# Sheet2.net
KiCad netlist of a schematic drawn in Altium Designer
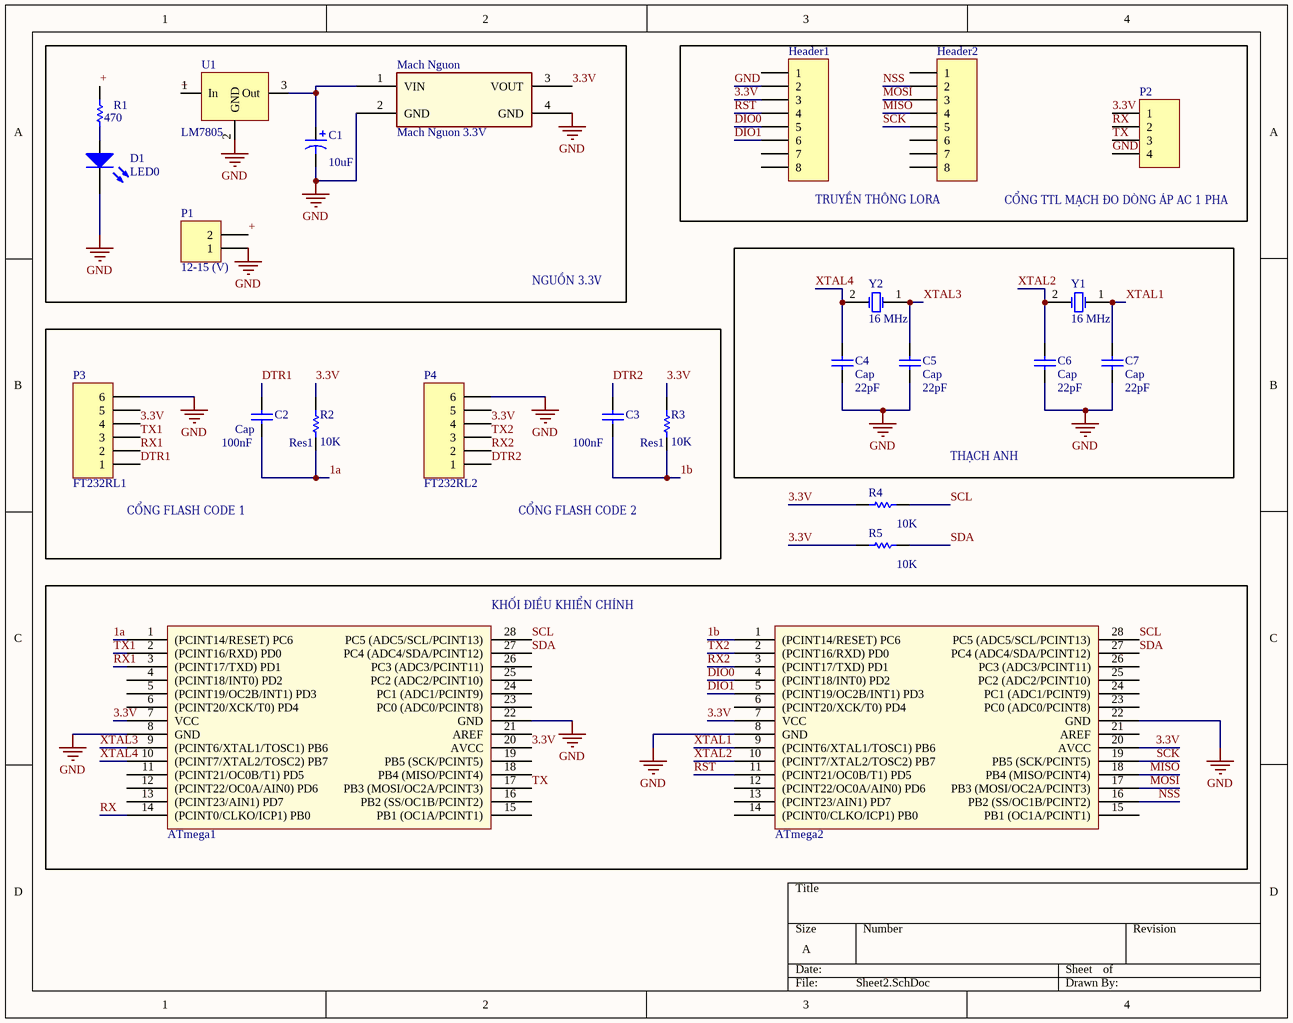
[diagram p0: Sheet2.SchDoc]

(export (version "E")
  (design (tool "Eeschema 10.0.6"))
  (components
    (comp (ref "ATmega1")
      (value "ATmega328P")
      (footprint "DIP794W46P254L2967H457Q28B")
      (libsource (lib "ATMEGA328") (part "ATmega328P"))
    )
    (comp (ref "ATmega2")
      (value "ATmega328P")
      (footprint "DIP794W46P254L2967H457Q28B")
      (libsource (lib "ATMEGA328") (part "ATmega328P"))
    )
    (comp (ref "C1")
      (value "10uF")
      (footprint "RB7.6-15")
      (description "Polarized Capacitor (Radial)")
      (fields (field (name "Comment") "Cap Pol1") (field (name "PUBLISHER") "Altium Limited"))
      (libsource (lib "Miscellaneous Devices") (part "Cap Pol1"))
    )
    (comp (ref "C2")
      (value "Cap")
      (footprint "RAD-0.3")
      (description "Capacitor")
      (fields (field (name "ALTIUM_VALUE") "100nF") (field (name "PUBLISHER") "Altium Limited"))
      (libsource (lib "Miscellaneous Devices") (part "Cap"))
    )
    (comp (ref "C3")
      (value "100nF")
      (footprint "RAD-0.3")
      (description "Capacitor")
      (fields (field (name "Comment") "Cap3") (field (name "PUBLISHER") "Altium Limited"))
      (libsource (lib "Miscellaneous Devices") (part "Cap"))
    )
    (comp (ref "C4")
      (value "Cap")
      (footprint "RAD-0.3")
      (description "Capacitor")
      (fields (field (name "ALTIUM_VALUE") "22pF") (field (name "PUBLISHER") "Altium Limited"))
      (libsource (lib "Miscellaneous Devices") (part "Cap"))
    )
    (comp (ref "C5")
      (value "Cap")
      (footprint "RAD-0.3")
      (description "Capacitor")
      (fields (field (name "ALTIUM_VALUE") "22pF") (field (name "PUBLISHER") "Altium Limited"))
      (libsource (lib "Miscellaneous Devices") (part "Cap"))
    )
    (comp (ref "C6")
      (value "Cap")
      (footprint "RAD-0.3")
      (description "Capacitor")
      (fields (field (name "ALTIUM_VALUE") "22pF") (field (name "PUBLISHER") "Altium Limited"))
      (libsource (lib "Miscellaneous Devices") (part "Cap"))
    )
    (comp (ref "C7")
      (value "Cap")
      (footprint "RAD-0.3")
      (description "Capacitor")
      (fields (field (name "ALTIUM_VALUE") "22pF") (field (name "PUBLISHER") "Altium Limited"))
      (libsource (lib "Miscellaneous Devices") (part "Cap"))
    )
    (comp (ref "D1")
      (value "LED0")
      (footprint "LED-0")
      (description "Typical INFRARED GaAs LED")
      (fields (field (name "PUBLISHER") "Altium Limited"))
      (libsource (lib "Miscellaneous Devices") (part "LED0"))
    )
    (comp (ref "Header1")
      (value "~")
      (footprint "HDR1X8")
      (description "Header, 8-Pin")
      (fields (field (name "PUBLISHER") "Altium Limited"))
      (libsource (lib "Miscellaneous Connectors") (part "Header 8"))
    )
    (comp (ref "Header2")
      (value "~")
      (footprint "HDR1X8")
      (description "Header, 8-Pin")
      (fields (field (name "PUBLISHER") "Altium Limited"))
      (libsource (lib "Miscellaneous Connectors") (part "Header 8"))
    )
    (comp (ref "Mach Nguon")
      (value "Mach Nguon 3.3V")
      (footprint "PCBComponent_1")
      (libsource (lib "MachNguon3.3V") (part "Component_1"))
    )
    (comp (ref "P1")
      (value "12-15 (V)")
      (footprint "HDR1X2")
      (description "Header, 2-Pin")
      (fields (field (name "PUBLISHER") "Altium Limited"))
      (libsource (lib "Miscellaneous Connectors") (part "Header 2"))
    )
    (comp (ref "P2")
      (value "Header 4")
      (footprint "HDR1X4")
      (description "Header, 4-Pin")
      (fields (field (name "PUBLISHER") "Altium Limited"))
      (libsource (lib "Miscellaneous Connectors") (part "Header 4"))
    )
    (comp (ref "P3")
      (value "FT232RL1")
      (footprint "HDR1X6")
      (description "Header, 6-Pin")
      (fields (field (name "PUBLISHER") "Altium Limited"))
      (libsource (lib "Miscellaneous Connectors") (part "Header 6"))
    )
    (comp (ref "P4")
      (value "FT232RL2")
      (footprint "HDR1X6")
      (description "Header, 6-Pin")
      (fields (field (name "PUBLISHER") "Altium Limited"))
      (libsource (lib "Miscellaneous Connectors") (part "Header 6"))
    )
    (comp (ref "R1")
      (value "470")
      (footprint "AXIAL-0.3")
      (description "Resistor")
      (fields (field (name "Comment") "Res1") (field (name "PUBLISHER") "Altium Limited"))
      (libsource (lib "Miscellaneous Devices") (part "Res1"))
    )
    (comp (ref "R2")
      (value "Res1")
      (footprint "AXIAL-0.3")
      (description "Resistor")
      (fields (field (name "ALTIUM_VALUE") "10K") (field (name "PUBLISHER") "Altium Limited"))
      (libsource (lib "Miscellaneous Devices") (part "Res1"))
    )
    (comp (ref "R3")
      (value "Res1")
      (footprint "AXIAL-0.3")
      (description "Resistor")
      (fields (field (name "ALTIUM_VALUE") "10K") (field (name "PUBLISHER") "Altium Limited"))
      (libsource (lib "Miscellaneous Devices") (part "Res1"))
    )
    (comp (ref "R4")
      (value "10K")
      (footprint "AXIAL-0.3")
      (description "Resistor")
      (fields (field (name "Comment") "Res1") (field (name "PUBLISHER") "Altium Limited"))
      (libsource (lib "Miscellaneous Devices") (part "Res1"))
    )
    (comp (ref "R5")
      (value "10K")
      (footprint "AXIAL-0.3")
      (description "Resistor")
      (fields (field (name "Comment") "Res1") (field (name "PUBLISHER") "Altium Limited"))
      (libsource (lib "Miscellaneous Devices") (part "Res1"))
    )
    (comp (ref "U1")
      (value "LM7805")
      (footprint "TO92-")
      (description "IC REG LIN 5V 1A")
      (libsource (lib "LM7805") (part "LM7805"))
    )
    (comp (ref "Y1")
      (value "16 MHz")
      (footprint "R38")
      (description "Crystal Oscillator")
      (fields (field (name "PUBLISHER") "Altium Limited"))
      (libsource (lib "Miscellaneous Devices") (part "XTAL"))
    )
    (comp (ref "Y2")
      (value "16 MHz")
      (footprint "R38")
      (description "Crystal Oscillator")
      (fields (field (name "PUBLISHER") "Altium Limited"))
      (libsource (lib "Miscellaneous Devices") (part "XTAL"))
    )
  )
  (nets
    (net (code "1") (name "/+") (class "Default")
      (node (ref "P1") (pin "2") (pinfunction "2_2") (pintype "passive"))
      (node (ref "R1") (pin "2") (pinfunction "2_2") (pintype "passive"))
      (node (ref "U1") (pin "1") (pinfunction "In_1") (pintype "passive"))
    )
    (net (code "2") (name "/1a") (class "Default")
      (node (ref "ATmega1") (pin "1") (pinfunction "(PCINT14/RESET)_PC6_1") (pintype "passive"))
      (node (ref "C2") (pin "1") (pinfunction "1_1") (pintype "passive"))
      (node (ref "R2") (pin "1") (pinfunction "1_1") (pintype "passive"))
    )
    (net (code "3") (name "/1b") (class "Default")
      (node (ref "ATmega2") (pin "1") (pinfunction "(PCINT14/RESET)_PC6_1") (pintype "passive"))
      (node (ref "C3") (pin "1") (pinfunction "1_1") (pintype "passive"))
      (node (ref "R3") (pin "1") (pinfunction "1_1") (pintype "passive"))
    )
    (net (code "4") (name "/3.3V") (class "Default")
      (node (ref "ATmega1") (pin "20") (pinfunction "AVCC_20") (pintype "passive"))
      (node (ref "ATmega1") (pin "7") (pinfunction "VCC_7") (pintype "passive"))
      (node (ref "ATmega2") (pin "20") (pinfunction "AVCC_20") (pintype "passive"))
      (node (ref "ATmega2") (pin "7") (pinfunction "VCC_7") (pintype "passive"))
      (node (ref "Header1") (pin "3") (pinfunction "3_3") (pintype "passive"))
      (node (ref "Mach Nguon") (pin "3") (pinfunction "VOUT_3") (pintype "passive"))
      (node (ref "P2") (pin "1") (pinfunction "1_1") (pintype "passive"))
      (node (ref "P3") (pin "4") (pinfunction "4_4") (pintype "passive"))
      (node (ref "P4") (pin "4") (pinfunction "4_4") (pintype "passive"))
      (node (ref "R2") (pin "2") (pinfunction "2_2") (pintype "passive"))
      (node (ref "R3") (pin "2") (pinfunction "2_2") (pintype "passive"))
      (node (ref "R4") (pin "1") (pinfunction "1_1") (pintype "passive"))
      (node (ref "R5") (pin "1") (pinfunction "1_1") (pintype "passive"))
    )
    (net (code "5") (name "/DIO0") (class "Default")
      (node (ref "ATmega2") (pin "4") (pinfunction "(PCINT18/INT0)_PD2_4") (pintype "passive"))
      (node (ref "Header1") (pin "5") (pinfunction "5_5") (pintype "passive"))
    )
    (net (code "6") (name "/DIO1") (class "Default")
      (node (ref "ATmega2") (pin "5") (pinfunction "(PCINT19/OC2B/INT1)_PD3_5") (pintype "passive"))
      (node (ref "Header1") (pin "6") (pinfunction "6_6") (pintype "passive"))
    )
    (net (code "7") (name "/DTR1") (class "Default")
      (node (ref "C2") (pin "2") (pinfunction "2_2") (pintype "passive"))
      (node (ref "P3") (pin "1") (pinfunction "1_1") (pintype "passive"))
    )
    (net (code "8") (name "/DTR2") (class "Default")
      (node (ref "C3") (pin "2") (pinfunction "2_2") (pintype "passive"))
      (node (ref "P4") (pin "1") (pinfunction "1_1") (pintype "passive"))
    )
    (net (code "9") (name "/MISO") (class "Default")
      (node (ref "ATmega2") (pin "18") (pinfunction "PB4_(MISO/PCINT4)_18") (pintype "passive"))
      (node (ref "Header2") (pin "4") (pinfunction "4_4") (pintype "passive"))
    )
    (net (code "10") (name "/MOSI") (class "Default")
      (node (ref "ATmega2") (pin "17") (pinfunction "PB3_(MOSI/OC2A/PCINT3)_17") (pintype "passive"))
      (node (ref "Header2") (pin "3") (pinfunction "3_3") (pintype "passive"))
    )
    (net (code "11") (name "/NSS") (class "Default")
      (node (ref "ATmega2") (pin "16") (pinfunction "PB2_(SS/OC1B/PCINT2)_16") (pintype "passive"))
      (node (ref "Header2") (pin "2") (pinfunction "2_2") (pintype "passive"))
    )
    (net (code "12") (name "/RST") (class "Default")
      (node (ref "ATmega2") (pin "11") (pinfunction "(PCINT21/OC0B/T1)_PD5_11") (pintype "passive"))
      (node (ref "Header1") (pin "4") (pinfunction "4_4") (pintype "passive"))
    )
    (net (code "13") (name "/RX") (class "Default")
      (node (ref "ATmega1") (pin "14") (pinfunction "(PCINT0/CLKO/ICP1)_PB0_14") (pintype "passive"))
      (node (ref "P2") (pin "2") (pinfunction "2_2") (pintype "passive"))
    )
    (net (code "14") (name "/RX1") (class "Default")
      (node (ref "ATmega1") (pin "3") (pinfunction "(PCINT17/TXD)_PD1_3") (pintype "passive"))
      (node (ref "P3") (pin "2") (pinfunction "2_2") (pintype "passive"))
    )
    (net (code "15") (name "/RX2") (class "Default")
      (node (ref "ATmega2") (pin "3") (pinfunction "(PCINT17/TXD)_PD1_3") (pintype "passive"))
      (node (ref "P4") (pin "2") (pinfunction "2_2") (pintype "passive"))
    )
    (net (code "16") (name "/SCK") (class "Default")
      (node (ref "ATmega2") (pin "19") (pinfunction "PB5_(SCK/PCINT5)_19") (pintype "passive"))
      (node (ref "Header2") (pin "5") (pinfunction "5_5") (pintype "passive"))
    )
    (net (code "17") (name "/SCL") (class "Default")
      (node (ref "ATmega1") (pin "28") (pinfunction "PC5_(ADC5/SCL/PCINT13)_28") (pintype "passive"))
      (node (ref "ATmega2") (pin "28") (pinfunction "PC5_(ADC5/SCL/PCINT13)_28") (pintype "passive"))
      (node (ref "R4") (pin "2") (pinfunction "2_2") (pintype "passive"))
    )
    (net (code "18") (name "/SDA") (class "Default")
      (node (ref "ATmega1") (pin "27") (pinfunction "PC4_(ADC4/SDA/PCINT12)_27") (pintype "passive"))
      (node (ref "ATmega2") (pin "27") (pinfunction "PC4_(ADC4/SDA/PCINT12)_27") (pintype "passive"))
      (node (ref "R5") (pin "2") (pinfunction "2_2") (pintype "passive"))
    )
    (net (code "19") (name "/TX") (class "Default")
      (node (ref "ATmega1") (pin "17") (pinfunction "PB3_(MOSI/OC2A/PCINT3)_17") (pintype "passive"))
      (node (ref "P2") (pin "3") (pinfunction "3_3") (pintype "passive"))
    )
    (net (code "20") (name "/TX1") (class "Default")
      (node (ref "ATmega1") (pin "2") (pinfunction "(PCINT16/RXD)_PD0_2") (pintype "passive"))
      (node (ref "P3") (pin "3") (pinfunction "3_3") (pintype "passive"))
    )
    (net (code "21") (name "/TX2") (class "Default")
      (node (ref "ATmega2") (pin "2") (pinfunction "(PCINT16/RXD)_PD0_2") (pintype "passive"))
      (node (ref "P4") (pin "3") (pinfunction "3_3") (pintype "passive"))
    )
    (net (code "22") (name "/XTAL1") (class "Default")
      (node (ref "ATmega2") (pin "9") (pinfunction "(PCINT6/XTAL1/TOSC1)_PB6_9") (pintype "passive"))
      (node (ref "C7") (pin "2") (pinfunction "2_2") (pintype "passive"))
      (node (ref "Y1") (pin "1") (pinfunction "OSC1_1") (pintype "passive"))
    )
    (net (code "23") (name "/XTAL2") (class "Default")
      (node (ref "ATmega2") (pin "10") (pinfunction "(PCINT7/XTAL2/TOSC2)_PB7_10") (pintype "passive"))
      (node (ref "C6") (pin "2") (pinfunction "2_2") (pintype "passive"))
      (node (ref "Y1") (pin "2") (pinfunction "OSC2_2") (pintype "passive"))
    )
    (net (code "24") (name "/XTAL3") (class "Default")
      (node (ref "ATmega1") (pin "9") (pinfunction "(PCINT6/XTAL1/TOSC1)_PB6_9") (pintype "passive"))
      (node (ref "C5") (pin "2") (pinfunction "2_2") (pintype "passive"))
      (node (ref "Y2") (pin "1") (pinfunction "OSC1_1") (pintype "passive"))
    )
    (net (code "25") (name "/XTAL4") (class "Default")
      (node (ref "ATmega1") (pin "10") (pinfunction "(PCINT7/XTAL2/TOSC2)_PB7_10") (pintype "passive"))
      (node (ref "C4") (pin "2") (pinfunction "2_2") (pintype "passive"))
      (node (ref "Y2") (pin "2") (pinfunction "OSC2_2") (pintype "passive"))
    )
    (net (code "26") (name "GND") (class "Default")
      (node (ref "ATmega1") (pin "22") (pinfunction "GND_22") (pintype "passive"))
      (node (ref "ATmega1") (pin "8") (pinfunction "GND_8") (pintype "passive"))
      (node (ref "ATmega2") (pin "22") (pinfunction "GND_22") (pintype "passive"))
      (node (ref "ATmega2") (pin "8") (pinfunction "GND_8") (pintype "passive"))
      (node (ref "C1") (pin "2") (pinfunction "2_2") (pintype "passive"))
      (node (ref "C4") (pin "1") (pinfunction "1_1") (pintype "passive"))
      (node (ref "C5") (pin "1") (pinfunction "1_1") (pintype "passive"))
      (node (ref "C6") (pin "1") (pinfunction "1_1") (pintype "passive"))
      (node (ref "C7") (pin "1") (pinfunction "1_1") (pintype "passive"))
      (node (ref "D1") (pin "2") (pinfunction "K_2") (pintype "passive"))
      (node (ref "Header1") (pin "2") (pinfunction "2_2") (pintype "passive"))
      (node (ref "Mach Nguon") (pin "2") (pinfunction "GND_2") (pintype "passive"))
      (node (ref "Mach Nguon") (pin "4") (pinfunction "GND_4") (pintype "passive"))
      (node (ref "P1") (pin "1") (pinfunction "1_1") (pintype "passive"))
      (node (ref "P2") (pin "4") (pinfunction "4_4") (pintype "passive"))
      (node (ref "P3") (pin "6") (pinfunction "6_6") (pintype "passive"))
      (node (ref "P4") (pin "6") (pinfunction "6_6") (pintype "passive"))
      (node (ref "U1") (pin "2") (pinfunction "GND_2") (pintype "passive"))
    )
    (net (code "27") (name "Net-(D1-A)") (class "Default")
      (node (ref "D1") (pin "1") (pinfunction "A_1") (pintype "passive"))
      (node (ref "R1") (pin "1") (pinfunction "1_1") (pintype "passive"))
    )
    (net (code "28") (name "Net-(Mach Nguon-VIN)") (class "Default")
      (node (ref "C1") (pin "1") (pinfunction "1_1") (pintype "passive"))
      (node (ref "Mach Nguon") (pin "1") (pinfunction "VIN_1") (pintype "passive"))
      (node (ref "U1") (pin "3") (pinfunction "Out_3") (pintype "passive"))
    )
    (net (code "29") (name "unconnected-(ATmega1-(PCINT18{slash}INT0)_PD2-Pad4)") (class "Default")
      (node (ref "ATmega1") (pin "4") (pinfunction "(PCINT18/INT0)_PD2_4") (pintype "passive"))
    )
    (net (code "30") (name "unconnected-(ATmega1-(PCINT19{slash}OC2B{slash}INT1)_PD3-Pad5)") (class "Default")
      (node (ref "ATmega1") (pin "5") (pinfunction "(PCINT19/OC2B/INT1)_PD3_5") (pintype "passive"))
    )
    (net (code "31") (name "unconnected-(ATmega1-(PCINT20{slash}XCK{slash}T0)_PD4-Pad6)") (class "Default")
      (node (ref "ATmega1") (pin "6") (pinfunction "(PCINT20/XCK/T0)_PD4_6") (pintype "passive"))
    )
    (net (code "32") (name "unconnected-(ATmega1-(PCINT21{slash}OC0B{slash}T1)_PD5-Pad11)") (class "Default")
      (node (ref "ATmega1") (pin "11") (pinfunction "(PCINT21/OC0B/T1)_PD5_11") (pintype "passive"))
    )
    (net (code "33") (name "unconnected-(ATmega1-(PCINT22{slash}OC0A{slash}AIN0)_PD6-Pad12)") (class "Default")
      (node (ref "ATmega1") (pin "12") (pinfunction "(PCINT22/OC0A/AIN0)_PD6_12") (pintype "passive"))
    )
    (net (code "34") (name "unconnected-(ATmega1-(PCINT23{slash}AIN1)_PD7-Pad13)") (class "Default")
      (node (ref "ATmega1") (pin "13") (pinfunction "(PCINT23/AIN1)_PD7_13") (pintype "passive"))
    )
    (net (code "35") (name "unconnected-(ATmega1-AREF-Pad21)") (class "Default")
      (node (ref "ATmega1") (pin "21") (pinfunction "AREF_21") (pintype "passive"))
    )
    (net (code "36") (name "unconnected-(ATmega1-PB1_(OC1A{slash}PCINT1)-Pad15)") (class "Default")
      (node (ref "ATmega1") (pin "15") (pinfunction "PB1_(OC1A/PCINT1)_15") (pintype "passive"))
    )
    (net (code "37") (name "unconnected-(ATmega1-PB2_(SS{slash}OC1B{slash}PCINT2)-Pad16)") (class "Default")
      (node (ref "ATmega1") (pin "16") (pinfunction "PB2_(SS/OC1B/PCINT2)_16") (pintype "passive"))
    )
    (net (code "38") (name "unconnected-(ATmega1-PB4_(MISO{slash}PCINT4)-Pad18)") (class "Default")
      (node (ref "ATmega1") (pin "18") (pinfunction "PB4_(MISO/PCINT4)_18") (pintype "passive"))
    )
    (net (code "39") (name "unconnected-(ATmega1-PB5_(SCK{slash}PCINT5)-Pad19)") (class "Default")
      (node (ref "ATmega1") (pin "19") (pinfunction "PB5_(SCK/PCINT5)_19") (pintype "passive"))
    )
    (net (code "40") (name "unconnected-(ATmega1-PC0_(ADC0{slash}PCINT8)-Pad23)") (class "Default")
      (node (ref "ATmega1") (pin "23") (pinfunction "PC0_(ADC0/PCINT8)_23") (pintype "passive"))
    )
    (net (code "41") (name "unconnected-(ATmega1-PC1_(ADC1{slash}PCINT9)-Pad24)") (class "Default")
      (node (ref "ATmega1") (pin "24") (pinfunction "PC1_(ADC1/PCINT9)_24") (pintype "passive"))
    )
    (net (code "42") (name "unconnected-(ATmega1-PC2_(ADC2{slash}PCINT10)-Pad25)") (class "Default")
      (node (ref "ATmega1") (pin "25") (pinfunction "PC2_(ADC2/PCINT10)_25") (pintype "passive"))
    )
    (net (code "43") (name "unconnected-(ATmega1-PC3_(ADC3{slash}PCINT11)-Pad26)") (class "Default")
      (node (ref "ATmega1") (pin "26") (pinfunction "PC3_(ADC3/PCINT11)_26") (pintype "passive"))
    )
    (net (code "44") (name "unconnected-(ATmega2-(PCINT0{slash}CLKO{slash}ICP1)_PB0-Pad14)") (class "Default")
      (node (ref "ATmega2") (pin "14") (pinfunction "(PCINT0/CLKO/ICP1)_PB0_14") (pintype "passive"))
    )
    (net (code "45") (name "unconnected-(ATmega2-(PCINT20{slash}XCK{slash}T0)_PD4-Pad6)") (class "Default")
      (node (ref "ATmega2") (pin "6") (pinfunction "(PCINT20/XCK/T0)_PD4_6") (pintype "passive"))
    )
    (net (code "46") (name "unconnected-(ATmega2-(PCINT22{slash}OC0A{slash}AIN0)_PD6-Pad12)") (class "Default")
      (node (ref "ATmega2") (pin "12") (pinfunction "(PCINT22/OC0A/AIN0)_PD6_12") (pintype "passive"))
    )
    (net (code "47") (name "unconnected-(ATmega2-(PCINT23{slash}AIN1)_PD7-Pad13)") (class "Default")
      (node (ref "ATmega2") (pin "13") (pinfunction "(PCINT23/AIN1)_PD7_13") (pintype "passive"))
    )
    (net (code "48") (name "unconnected-(ATmega2-AREF-Pad21)") (class "Default")
      (node (ref "ATmega2") (pin "21") (pinfunction "AREF_21") (pintype "passive"))
    )
    (net (code "49") (name "unconnected-(ATmega2-PB1_(OC1A{slash}PCINT1)-Pad15)") (class "Default")
      (node (ref "ATmega2") (pin "15") (pinfunction "PB1_(OC1A/PCINT1)_15") (pintype "passive"))
    )
    (net (code "50") (name "unconnected-(ATmega2-PC0_(ADC0{slash}PCINT8)-Pad23)") (class "Default")
      (node (ref "ATmega2") (pin "23") (pinfunction "PC0_(ADC0/PCINT8)_23") (pintype "passive"))
    )
    (net (code "51") (name "unconnected-(ATmega2-PC1_(ADC1{slash}PCINT9)-Pad24)") (class "Default")
      (node (ref "ATmega2") (pin "24") (pinfunction "PC1_(ADC1/PCINT9)_24") (pintype "passive"))
    )
    (net (code "52") (name "unconnected-(ATmega2-PC2_(ADC2{slash}PCINT10)-Pad25)") (class "Default")
      (node (ref "ATmega2") (pin "25") (pinfunction "PC2_(ADC2/PCINT10)_25") (pintype "passive"))
    )
    (net (code "53") (name "unconnected-(ATmega2-PC3_(ADC3{slash}PCINT11)-Pad26)") (class "Default")
      (node (ref "ATmega2") (pin "26") (pinfunction "PC3_(ADC3/PCINT11)_26") (pintype "passive"))
    )
    (net (code "54") (name "unconnected-(Header1-Pad1)") (class "Default")
      (node (ref "Header1") (pin "1") (pinfunction "1_1") (pintype "passive"))
    )
    (net (code "55") (name "unconnected-(Header1-Pad7)") (class "Default")
      (node (ref "Header1") (pin "7") (pinfunction "7_7") (pintype "passive"))
    )
    (net (code "56") (name "unconnected-(Header1-Pad8)") (class "Default")
      (node (ref "Header1") (pin "8") (pinfunction "8_8") (pintype "passive"))
    )
    (net (code "57") (name "unconnected-(Header2-Pad1)") (class "Default")
      (node (ref "Header2") (pin "1") (pinfunction "1_1") (pintype "passive"))
    )
    (net (code "58") (name "unconnected-(Header2-Pad6)") (class "Default")
      (node (ref "Header2") (pin "6") (pinfunction "6_6") (pintype "passive"))
    )
    (net (code "59") (name "unconnected-(Header2-Pad7)") (class "Default")
      (node (ref "Header2") (pin "7") (pinfunction "7_7") (pintype "passive"))
    )
    (net (code "60") (name "unconnected-(Header2-Pad8)") (class "Default")
      (node (ref "Header2") (pin "8") (pinfunction "8_8") (pintype "passive"))
    )
    (net (code "61") (name "unconnected-(P3-Pad5)") (class "Default")
      (node (ref "P3") (pin "5") (pinfunction "5_5") (pintype "passive"))
    )
    (net (code "62") (name "unconnected-(P4-Pad5)") (class "Default")
      (node (ref "P4") (pin "5") (pinfunction "5_5") (pintype "passive"))
    )
  )
)
